# Sheet1.net
KiCad netlist of a schematic drawn in Altium Designer
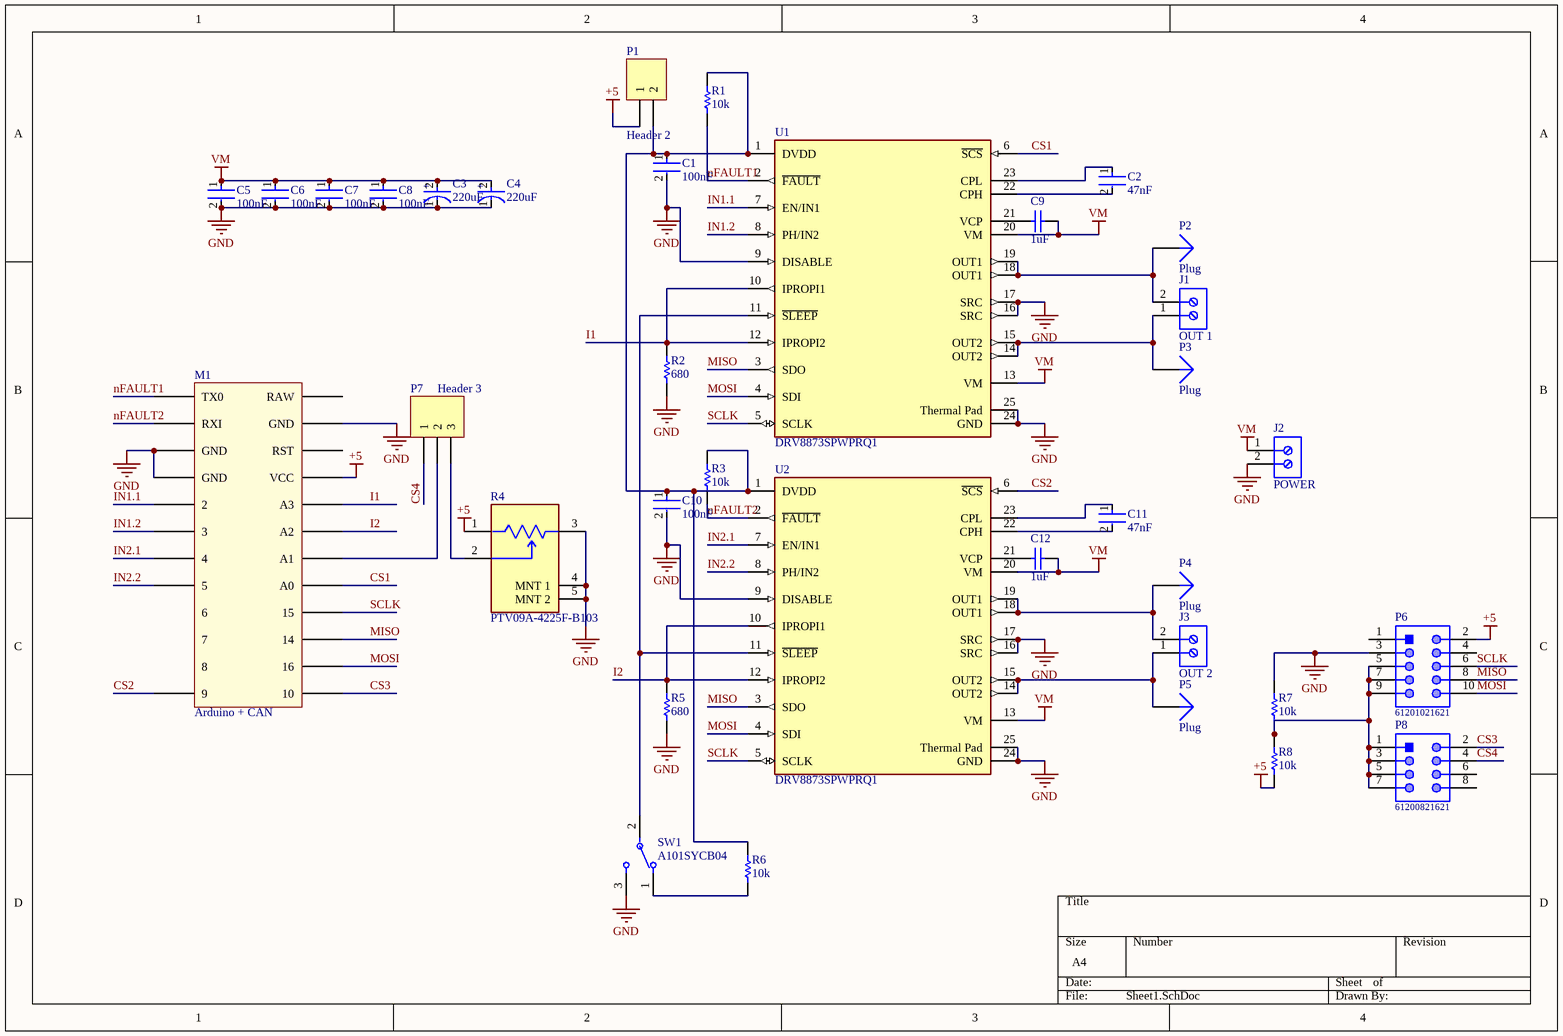
[diagram p0: Sheet1.SchDoc]

(export (version "E")
  (design (tool "Eeschema 10.0.6"))
  (components
    (comp (ref "C1")
      (value "100nF")
      (footprint "FP-0805-L_2_01_0_2-W_1_25-IPC_B")
      (description "General Purpose Ceramic Capacitor, 0805, 100nF, 10%, X7R, 15%, 100V")
      (fields (field (name "VOLTAGE") "100V") (field (name "TOLERANCE") "10%"))
      (libsource (lib "Altium Content Vault") (part "b4654b650e69147ec39a6b967a45e02"))
    )
    (comp (ref "C2")
      (value "47nF")
      (footprint "FP-C0805C-DN-MFG")
      (description "CAP CER 0.047UF 50V X7R 0805")
      (fields
        (field (name "MANUFACTURER PART NUMBER") "C0805C473K5RACTU")
        (field (name "OCTOPART") "https://octopart.com/c0805c473k5ractu-kemet-138387")
      )
      (libsource (lib "Altium Content Vault") (part "b4654b650e69147ec39a6b967a45e02"))
    )
    (comp (ref "C3")
      (value "220uF")
      (footprint "FP-UWT1V221MNL1GS-MFG")
      (description "CAP ALUM 220UF 20% 35V SMD")
      (fields (field (name "VOLTAGE") "35V") (field (name "TOLERANCE") "20%"))
      (libsource (lib "Altium Content Vault") (part "a00bbbee19879c290e62620ae7e47b1"))
    )
    (comp (ref "C4")
      (value "220uF")
      (footprint "FP-UWT1V221MNL1GS-MFG")
      (description "CAP ALUM 220UF 20% 35V SMD")
      (fields (field (name "VOLTAGE") "35V") (field (name "TOLERANCE") "20%"))
      (libsource (lib "Altium Content Vault") (part "a00bbbee19879c290e62620ae7e47b1"))
    )
    (comp (ref "C5")
      (value "100nF")
      (footprint "FP-0805-L_2_01_0_2-W_1_25-IPC_B")
      (description "General Purpose Ceramic Capacitor, 0805, 100nF, 10%, X7R, 15%, 100V")
      (fields (field (name "VOLTAGE") "100V") (field (name "TOLERANCE") "10%"))
      (libsource (lib "Altium Content Vault") (part "b4654b650e69147ec39a6b967a45e02"))
    )
    (comp (ref "C6")
      (value "100nF")
      (footprint "FP-0805-L_2_01_0_2-W_1_25-IPC_B")
      (description "General Purpose Ceramic Capacitor, 0805, 100nF, 10%, X7R, 15%, 100V")
      (fields (field (name "VOLTAGE") "100V") (field (name "TOLERANCE") "10%"))
      (libsource (lib "Altium Content Vault") (part "b4654b650e69147ec39a6b967a45e02"))
    )
    (comp (ref "C7")
      (value "100nF")
      (footprint "FP-0805-L_2_01_0_2-W_1_25-IPC_B")
      (description "General Purpose Ceramic Capacitor, 0805, 100nF, 10%, X7R, 15%, 100V")
      (fields (field (name "VOLTAGE") "100V") (field (name "TOLERANCE") "10%"))
      (libsource (lib "Altium Content Vault") (part "b4654b650e69147ec39a6b967a45e02"))
    )
    (comp (ref "C8")
      (value "100nF")
      (footprint "FP-0805-L_2_01_0_2-W_1_25-IPC_B")
      (description "General Purpose Ceramic Capacitor, 0805, 100nF, 10%, X7R, 15%, 100V")
      (fields (field (name "VOLTAGE") "100V") (field (name "TOLERANCE") "10%"))
      (libsource (lib "Altium Content Vault") (part "b4654b650e69147ec39a6b967a45e02"))
    )
    (comp (ref "C9")
      (value "1uF")
      (footprint "CAPC2013X145X50LL20T25")
      (fields (field (name "MANUFACTURER") "Kemet") (field (name "PART NUMBER") "C0805C105K4PACTU"))
      (libsource (lib "Altium Content Vault") (part "CAP"))
    )
    (comp (ref "C10")
      (value "100nF")
      (footprint "FP-0805-L_2_01_0_2-W_1_25-IPC_B")
      (description "General Purpose Ceramic Capacitor, 0805, 100nF, 10%, X7R, 15%, 100V")
      (fields (field (name "VOLTAGE") "100V") (field (name "TOLERANCE") "10%"))
      (libsource (lib "Altium Content Vault") (part "b4654b650e69147ec39a6b967a45e02"))
    )
    (comp (ref "C11")
      (value "47nF")
      (footprint "FP-C0805C-DN-MFG")
      (description "CAP CER 0.047UF 50V X7R 0805")
      (fields
        (field (name "MANUFACTURER PART NUMBER") "C0805C473K5RACTU")
        (field (name "OCTOPART") "https://octopart.com/c0805c473k5ractu-kemet-138387")
      )
      (libsource (lib "Altium Content Vault") (part "b4654b650e69147ec39a6b967a45e02"))
    )
    (comp (ref "C12")
      (value "1uF")
      (footprint "CAPC2013X145X50LL20T25")
      (fields (field (name "MANUFACTURER") "Kemet") (field (name "PART NUMBER") "C0805C105K4PACTU"))
      (libsource (lib "Altium Content Vault") (part "CAP"))
    )
    (comp (ref "J1")
      (value "OUT 1")
      (footprint "691102710002")
      (fields (field (name "VOLTAGE") "300V"))
      (libsource (lib "Altium Content Vault") (part "TBL - 1R - 02P - Screw"))
    )
    (comp (ref "J2")
      (value "POWER")
      (footprint "691102710002")
      (fields (field (name "VOLTAGE") "300V"))
      (libsource (lib "Altium Content Vault") (part "TBL - 1R - 02P - Screw"))
    )
    (comp (ref "J3")
      (value "OUT 2")
      (footprint "691102710002")
      (fields (field (name "VOLTAGE") "300V"))
      (libsource (lib "Altium Content Vault") (part "TBL - 1R - 02P - Screw"))
    )
    (comp (ref "M1")
      (value "Arduino + CAN")
      (footprint "PCBComponent_1")
      (description "Arduino Pro Micro + CAN Shield")
      (libsource (lib "Arduino") (part "Arduino"))
    )
    (comp (ref "P1")
      (value "Header 2")
      (footprint "HDR1X2")
      (description "Header, 2-Pin")
      (fields (field (name "PUBLISHER") "Altium Limited"))
      (libsource (lib "Miscellaneous Connectors") (part "Header 2"))
    )
    (comp (ref "P2")
      (value "Plug")
      (footprint "PIN1")
      (fields (field (name "PUBLISHER") "Altium Limited"))
      (libsource (lib "Miscellaneous Connectors") (part "Plug"))
    )
    (comp (ref "P3")
      (value "Plug")
      (footprint "PIN1")
      (fields (field (name "PUBLISHER") "Altium Limited"))
      (libsource (lib "Miscellaneous Connectors") (part "Plug"))
    )
    (comp (ref "P4")
      (value "Plug")
      (footprint "PIN1")
      (fields (field (name "PUBLISHER") "Altium Limited"))
      (libsource (lib "Miscellaneous Connectors") (part "Plug"))
    )
    (comp (ref "P5")
      (value "Plug")
      (footprint "PIN1")
      (fields (field (name "PUBLISHER") "Altium Limited"))
      (libsource (lib "Miscellaneous Connectors") (part "Plug"))
    )
    (comp (ref "P6")
      (value "61201021621")
      (footprint "61201021621")
      (description "Male Box Header WR-BHD, THT, Vertical, pitch 2.54 mm, 10 pins")
      (fields (field (name "MANUFACTURER") "Wurth Elektronik") (field (name "PUBLISHER") "WurthElektronik"))
      (libsource (lib "Altium Content Vault") (part "WE-CN-2P-M-R10"))
    )
    (comp (ref "P7")
      (value "Header 3")
      (footprint "HDR1X3")
      (description "Header, 3-Pin")
      (fields (field (name "PUBLISHER") "Altium Limited"))
      (libsource (lib "Miscellaneous Connectors") (part "Header 3"))
    )
    (comp (ref "P8")
      (value "61200821621")
      (footprint "61200821621")
      (description "Male Box Header WR-BHD, THT, Vertical, pitch 2.54 mm, 8 pins")
      (fields (field (name "MANUFACTURER") "Wurth Elektronik") (field (name "PUBLISHER") "WurthElektronik"))
      (libsource (lib "Altium Content Vault") (part "WE-CN-2P-M-R8"))
    )
    (comp (ref "R1")
      (value "10k")
      (footprint "RESC2013X60X35NL10T20")
      (description "Chip Resistor, 10 KOhm, +/- 1%, 0.125 W, -55 to 155 degC, 0805 (2012 Metric), RoHS, Tape and Reel")
      (fields (field (name "MANUFACTURER") "Yageo"))
      (libsource (lib "Altium Content Vault") (part "RES-2"))
    )
    (comp (ref "R2")
      (value "680")
      (footprint "RESC2013X60X35NL10T20")
      (description "Chip Resistor, 10 KOhm, +/- 1%, 0.125 W, -55 to 155 degC, 0805 (2012 Metric), RoHS, Tape and Reel")
      (fields (field (name "MANUFACTURER") "Yageo"))
      (libsource (lib "Altium Content Vault") (part "RES-2"))
    )
    (comp (ref "R3")
      (value "10k")
      (footprint "RESC2013X60X35NL10T20")
      (description "Chip Resistor, 10 KOhm, +/- 1%, 0.125 W, -55 to 155 degC, 0805 (2012 Metric), RoHS, Tape and Reel")
      (fields (field (name "MANUFACTURER") "Yageo"))
      (libsource (lib "Altium Content Vault") (part "RES-2"))
    )
    (comp (ref "R4")
      (value "PTV09A-4225F-B103")
      (footprint "FP-PTV09A-4-MFG")
      (description "POT 10K OHM 1/20W CARBON LINEAR")
      (fields (field (name "TOLERANCE") "20%"))
      (libsource (lib "Altium Content Vault") (part "705d11b747745a787204d796a5f3d12"))
    )
    (comp (ref "R5")
      (value "680")
      (footprint "RESC2013X60X35NL10T20")
      (description "Chip Resistor, 10 KOhm, +/- 1%, 0.125 W, -55 to 155 degC, 0805 (2012 Metric), RoHS, Tape and Reel")
      (fields (field (name "MANUFACTURER") "Yageo"))
      (libsource (lib "Altium Content Vault") (part "RES-2"))
    )
    (comp (ref "R6")
      (value "10k")
      (footprint "RESC2013X60X35NL10T20")
      (description "Chip Resistor, 10 KOhm, +/- 1%, 0.125 W, -55 to 155 degC, 0805 (2012 Metric), RoHS, Tape and Reel")
      (fields (field (name "MANUFACTURER") "Yageo"))
      (libsource (lib "Altium Content Vault") (part "RES-2"))
    )
    (comp (ref "R7")
      (value "10k")
      (footprint "RESC2013X60X35NL10T20")
      (description "Chip Resistor, 10 KOhm, +/- 1%, 0.125 W, -55 to 155 degC, 0805 (2012 Metric), RoHS, Tape and Reel")
      (fields (field (name "MANUFACTURER") "Yageo"))
      (libsource (lib "Altium Content Vault") (part "RES-2"))
    )
    (comp (ref "R8")
      (value "10k")
      (footprint "RESC2013X60X35NL10T20")
      (description "Chip Resistor, 10 KOhm, +/- 1%, 0.125 W, -55 to 155 degC, 0805 (2012 Metric), RoHS, Tape and Reel")
      (fields (field (name "MANUFACTURER") "Yageo"))
      (libsource (lib "Altium Content Vault") (part "RES-2"))
    )
    (comp (ref "SW1")
      (value "A101SYCB04")
      (footprint "FP-A101SYCB04-MFG")
      (description "SWITCH TOGGLE SPDT 0.4VA 20V")
      (libsource (lib "Altium Content Vault") (part "52c419afdc2a387c7d548259a9aeefb"))
    )
    (comp (ref "U1")
      (value "DRV8873SPWPRQ1")
      (footprint "FP-PWP0024J-MFG")
      (description "IC MTRDRV UNIPLR 0-5.5V 24HTSSOP")
      (libsource (lib "Altium Content Vault") (part "639cfc0396780f9562c68c0b1c9b09f"))
    )
    (comp (ref "U2")
      (value "DRV8873SPWPRQ1")
      (footprint "FP-PWP0024J-MFG")
      (description "IC MTRDRV UNIPLR 0-5.5V 24HTSSOP")
      (libsource (lib "Altium Content Vault") (part "639cfc0396780f9562c68c0b1c9b09f"))
    )
  )
  (nets
    (net (code "1") (name "+5") (class "Default")
      (node (ref "M1") (pin "21") (pinfunction "VCC_21") (pintype "passive"))
      (node (ref "P1") (pin "1") (pinfunction "1_1") (pintype "passive"))
      (node (ref "P6") (pin "2") (pinfunction "2_2") (pintype "passive"))
      (node (ref "R4") (pin "1") (pinfunction "1_1") (pintype "passive"))
      (node (ref "R8") (pin "1") (pinfunction "1_1") (pintype "passive"))
    )
    (net (code "2") (name "/CS1") (class "Default")
      (node (ref "M1") (pin "17") (pinfunction "A0_17") (pintype "passive"))
      (node (ref "U1") (pin "6") (pinfunction "~{SCS}_6") (pintype "input"))
    )
    (net (code "3") (name "/CS2") (class "Default")
      (node (ref "M1") (pin "12") (pinfunction "9_12") (pintype "passive"))
      (node (ref "U2") (pin "6") (pinfunction "~{SCS}_6") (pintype "input"))
    )
    (net (code "4") (name "/CS3") (class "Default")
      (node (ref "M1") (pin "13") (pinfunction "10_13") (pintype "passive"))
      (node (ref "P8") (pin "2") (pinfunction "2_2") (pintype "passive"))
    )
    (net (code "5") (name "/CS4") (class "Default")
      (node (ref "P7") (pin "1") (pinfunction "1_1") (pintype "passive"))
      (node (ref "P8") (pin "4") (pinfunction "4_4") (pintype "passive"))
    )
    (net (code "6") (name "/I1") (class "Default")
      (node (ref "M1") (pin "20") (pinfunction "A3_20") (pintype "passive"))
      (node (ref "R2") (pin "2") (pinfunction "2_2") (pintype "passive"))
      (node (ref "U1") (pin "10") (pinfunction "IPROPI1_10") (pintype "output"))
      (node (ref "U1") (pin "12") (pinfunction "IPROPI2_12") (pintype "input"))
    )
    (net (code "7") (name "/I2") (class "Default")
      (node (ref "M1") (pin "19") (pinfunction "A2_19") (pintype "passive"))
      (node (ref "R5") (pin "2") (pinfunction "2_2") (pintype "passive"))
      (node (ref "U2") (pin "10") (pinfunction "IPROPI1_10") (pintype "output"))
      (node (ref "U2") (pin "12") (pinfunction "IPROPI2_12") (pintype "input"))
    )
    (net (code "8") (name "/IN1.1") (class "Default")
      (node (ref "M1") (pin "5") (pinfunction "2_5") (pintype "passive"))
      (node (ref "U1") (pin "7") (pinfunction "EN/IN1_7") (pintype "input"))
    )
    (net (code "9") (name "/IN1.2") (class "Default")
      (node (ref "M1") (pin "6") (pinfunction "3_6") (pintype "passive"))
      (node (ref "U1") (pin "8") (pinfunction "PH/IN2_8") (pintype "input"))
    )
    (net (code "10") (name "/IN2.1") (class "Default")
      (node (ref "M1") (pin "7") (pinfunction "4_7") (pintype "passive"))
      (node (ref "U2") (pin "7") (pinfunction "EN/IN1_7") (pintype "input"))
    )
    (net (code "11") (name "/IN2.2") (class "Default")
      (node (ref "M1") (pin "8") (pinfunction "5_8") (pintype "passive"))
      (node (ref "U2") (pin "8") (pinfunction "PH/IN2_8") (pintype "input"))
    )
    (net (code "12") (name "/MISO") (class "Default")
      (node (ref "M1") (pin "15") (pinfunction "14_15") (pintype "passive"))
      (node (ref "P6") (pin "8") (pinfunction "8_8") (pintype "passive"))
      (node (ref "U1") (pin "3") (pinfunction "SDO_3") (pintype "output"))
      (node (ref "U2") (pin "3") (pinfunction "SDO_3") (pintype "output"))
    )
    (net (code "13") (name "/MOSI") (class "Default")
      (node (ref "M1") (pin "14") (pinfunction "16_14") (pintype "passive"))
      (node (ref "P6") (pin "10") (pinfunction "10_10") (pintype "passive"))
      (node (ref "U1") (pin "4") (pinfunction "SDI_4") (pintype "input"))
      (node (ref "U2") (pin "4") (pinfunction "SDI_4") (pintype "input"))
    )
    (net (code "14") (name "/SCLK") (class "Default")
      (node (ref "M1") (pin "16") (pinfunction "15_16") (pintype "passive"))
      (node (ref "P6") (pin "6") (pinfunction "6_6") (pintype "passive"))
      (node (ref "U1") (pin "5") (pinfunction "SCLK_5") (pintype "bidirectional"))
      (node (ref "U2") (pin "5") (pinfunction "SCLK_5") (pintype "bidirectional"))
    )
    (net (code "15") (name "/nFAULT1") (class "Default")
      (node (ref "M1") (pin "1") (pinfunction "TX0_1") (pintype "passive"))
      (node (ref "R1") (pin "1") (pinfunction "1_1") (pintype "passive"))
      (node (ref "U1") (pin "2") (pinfunction "~{FAULT}_2") (pintype "output"))
    )
    (net (code "16") (name "/nFAULT2") (class "Default")
      (node (ref "M1") (pin "2") (pinfunction "RXI_2") (pintype "passive"))
      (node (ref "R3") (pin "1") (pinfunction "1_1") (pintype "passive"))
      (node (ref "U2") (pin "2") (pinfunction "~{FAULT}_2") (pintype "output"))
    )
    (net (code "17") (name "GND") (class "Default")
      (node (ref "C1") (pin "2") (pinfunction "2_2") (pintype "passive"))
      (node (ref "C10") (pin "2") (pinfunction "2_2") (pintype "passive"))
      (node (ref "C3") (pin "1") (pinfunction "C_1") (pintype "passive"))
      (node (ref "C4") (pin "1") (pinfunction "C_1") (pintype "passive"))
      (node (ref "C5") (pin "2") (pinfunction "2_2") (pintype "passive"))
      (node (ref "C6") (pin "2") (pinfunction "2_2") (pintype "passive"))
      (node (ref "C7") (pin "2") (pinfunction "2_2") (pintype "passive"))
      (node (ref "C8") (pin "2") (pinfunction "2_2") (pintype "passive"))
      (node (ref "J2") (pin "2") (pinfunction "2_2") (pintype "passive"))
      (node (ref "M1") (pin "23") (pinfunction "GND_23") (pintype "passive"))
      (node (ref "M1") (pin "3") (pinfunction "GND_3") (pintype "passive"))
      (node (ref "M1") (pin "4") (pinfunction "GND_4") (pintype "passive"))
      (node (ref "P6") (pin "3") (pinfunction "3_3") (pintype "passive"))
      (node (ref "R2") (pin "1") (pinfunction "1_1") (pintype "passive"))
      (node (ref "R4") (pin "3") (pinfunction "3_3") (pintype "passive"))
      (node (ref "R4") (pin "4") (pinfunction "MNT_1_4") (pintype "passive"))
      (node (ref "R4") (pin "5") (pinfunction "MNT_2_5") (pintype "passive"))
      (node (ref "R5") (pin "1") (pinfunction "1_1") (pintype "passive"))
      (node (ref "R7") (pin "2") (pinfunction "2_2") (pintype "passive"))
      (node (ref "SW1") (pin "3") (pinfunction "3_3") (pintype "passive"))
      (node (ref "U1") (pin "16") (pinfunction "SRC_16") (pintype "output"))
      (node (ref "U1") (pin "17") (pinfunction "SRC_17") (pintype "output"))
      (node (ref "U1") (pin "24") (pinfunction "GND_24") (pintype "power_in"))
      (node (ref "U1") (pin "25") (pinfunction "Thermal_Pad_25") (pintype "power_in"))
      (node (ref "U1") (pin "9") (pinfunction "DISABLE_9") (pintype "input"))
      (node (ref "U2") (pin "16") (pinfunction "SRC_16") (pintype "output"))
      (node (ref "U2") (pin "17") (pinfunction "SRC_17") (pintype "output"))
      (node (ref "U2") (pin "24") (pinfunction "GND_24") (pintype "power_in"))
      (node (ref "U2") (pin "25") (pinfunction "Thermal_Pad_25") (pintype "power_in"))
      (node (ref "U2") (pin "9") (pinfunction "DISABLE_9") (pintype "input"))
    )
    (net (code "18") (name "Net-(J1-Pad1)") (class "Default")
      (node (ref "J1") (pin "1") (pinfunction "1_1") (pintype "passive"))
      (node (ref "P3") (pin "1") (pinfunction "1_1") (pintype "passive"))
      (node (ref "U1") (pin "14") (pinfunction "OUT2_14") (pintype "output"))
      (node (ref "U1") (pin "15") (pinfunction "OUT2_15") (pintype "output"))
    )
    (net (code "19") (name "Net-(J1-Pad2)") (class "Default")
      (node (ref "J1") (pin "2") (pinfunction "2_2") (pintype "passive"))
      (node (ref "P2") (pin "1") (pinfunction "1_1") (pintype "passive"))
      (node (ref "U1") (pin "18") (pinfunction "OUT1_18") (pintype "output"))
      (node (ref "U1") (pin "19") (pinfunction "OUT1_19") (pintype "output"))
    )
    (net (code "20") (name "Net-(J3-Pad1)") (class "Default")
      (node (ref "J3") (pin "1") (pinfunction "1_1") (pintype "passive"))
      (node (ref "P5") (pin "1") (pinfunction "1_1") (pintype "passive"))
      (node (ref "U2") (pin "14") (pinfunction "OUT2_14") (pintype "output"))
      (node (ref "U2") (pin "15") (pinfunction "OUT2_15") (pintype "output"))
    )
    (net (code "21") (name "Net-(J3-Pad2)") (class "Default")
      (node (ref "J3") (pin "2") (pinfunction "2_2") (pintype "passive"))
      (node (ref "P4") (pin "1") (pinfunction "1_1") (pintype "passive"))
      (node (ref "U2") (pin "18") (pinfunction "OUT1_18") (pintype "output"))
      (node (ref "U2") (pin "19") (pinfunction "OUT1_19") (pintype "output"))
    )
    (net (code "22") (name "Net-(M1-A1)") (class "Default")
      (node (ref "M1") (pin "18") (pinfunction "A1_18") (pintype "passive"))
      (node (ref "P7") (pin "2") (pinfunction "2_2") (pintype "passive"))
    )
    (net (code "23") (name "Net-(P6-Pad5)") (class "Default")
      (node (ref "P6") (pin "5") (pinfunction "5_5") (pintype "passive"))
      (node (ref "P6") (pin "7") (pinfunction "7_7") (pintype "passive"))
      (node (ref "P6") (pin "9") (pinfunction "9_9") (pintype "passive"))
      (node (ref "P8") (pin "1") (pinfunction "1_1") (pintype "passive"))
      (node (ref "P8") (pin "3") (pinfunction "3_3") (pintype "passive"))
      (node (ref "P8") (pin "5") (pinfunction "5_5") (pintype "passive"))
      (node (ref "P8") (pin "7") (pinfunction "7_7") (pintype "passive"))
      (node (ref "R7") (pin "1") (pinfunction "1_1") (pintype "passive"))
      (node (ref "R8") (pin "2") (pinfunction "2_2") (pintype "passive"))
    )
    (net (code "24") (name "Net-(P7-Pad3)") (class "Default")
      (node (ref "P7") (pin "3") (pinfunction "3_3") (pintype "passive"))
      (node (ref "R4") (pin "2") (pinfunction "2_2") (pintype "passive"))
    )
    (net (code "25") (name "Net-(R6-Pad1)") (class "Default")
      (node (ref "R6") (pin "1") (pinfunction "1_1") (pintype "passive"))
      (node (ref "SW1") (pin "1") (pinfunction "1_1") (pintype "passive"))
    )
    (net (code "26") (name "Net-(U1-CPH)") (class "Default")
      (node (ref "C2") (pin "2") (pinfunction "2_2") (pintype "passive"))
      (node (ref "U1") (pin "22") (pinfunction "CPH_22") (pintype "power_in"))
    )
    (net (code "27") (name "Net-(U1-CPL)") (class "Default")
      (node (ref "C2") (pin "1") (pinfunction "1_1") (pintype "passive"))
      (node (ref "U1") (pin "23") (pinfunction "CPL_23") (pintype "power_in"))
    )
    (net (code "28") (name "Net-(U1-DVDD)") (class "Default")
      (node (ref "C1") (pin "1") (pinfunction "1_1") (pintype "passive"))
      (node (ref "C10") (pin "1") (pinfunction "1_1") (pintype "passive"))
      (node (ref "P1") (pin "2") (pinfunction "2_2") (pintype "passive"))
      (node (ref "R1") (pin "2") (pinfunction "2_2") (pintype "passive"))
      (node (ref "R3") (pin "2") (pinfunction "2_2") (pintype "passive"))
      (node (ref "R6") (pin "2") (pinfunction "2_2") (pintype "passive"))
      (node (ref "U1") (pin "1") (pinfunction "DVDD_1") (pintype "power_in"))
      (node (ref "U2") (pin "1") (pinfunction "DVDD_1") (pintype "power_in"))
    )
    (net (code "29") (name "Net-(U1-VCP)") (class "Default")
      (node (ref "C9") (pin "1") (pinfunction "1_1") (pintype "passive"))
      (node (ref "U1") (pin "21") (pinfunction "VCP_21") (pintype "power_in"))
    )
    (net (code "30") (name "Net-(U1-~{SLEEP})") (class "Default")
      (node (ref "SW1") (pin "2") (pinfunction "2_2") (pintype "passive"))
      (node (ref "U1") (pin "11") (pinfunction "~{SLEEP}_11") (pintype "input"))
      (node (ref "U2") (pin "11") (pinfunction "~{SLEEP}_11") (pintype "input"))
    )
    (net (code "31") (name "Net-(U2-CPH)") (class "Default")
      (node (ref "C11") (pin "2") (pinfunction "2_2") (pintype "passive"))
      (node (ref "U2") (pin "22") (pinfunction "CPH_22") (pintype "power_in"))
    )
    (net (code "32") (name "Net-(U2-CPL)") (class "Default")
      (node (ref "C11") (pin "1") (pinfunction "1_1") (pintype "passive"))
      (node (ref "U2") (pin "23") (pinfunction "CPL_23") (pintype "power_in"))
    )
    (net (code "33") (name "Net-(U2-VCP)") (class "Default")
      (node (ref "C12") (pin "1") (pinfunction "1_1") (pintype "passive"))
      (node (ref "U2") (pin "21") (pinfunction "VCP_21") (pintype "power_in"))
    )
    (net (code "34") (name "VM") (class "Default")
      (node (ref "C12") (pin "2") (pinfunction "2_2") (pintype "passive"))
      (node (ref "C3") (pin "2") (pinfunction "A_2") (pintype "passive"))
      (node (ref "C4") (pin "2") (pinfunction "A_2") (pintype "passive"))
      (node (ref "C5") (pin "1") (pinfunction "1_1") (pintype "passive"))
      (node (ref "C6") (pin "1") (pinfunction "1_1") (pintype "passive"))
      (node (ref "C7") (pin "1") (pinfunction "1_1") (pintype "passive"))
      (node (ref "C8") (pin "1") (pinfunction "1_1") (pintype "passive"))
      (node (ref "C9") (pin "2") (pinfunction "2_2") (pintype "passive"))
      (node (ref "J2") (pin "1") (pinfunction "1_1") (pintype "passive"))
      (node (ref "U1") (pin "13") (pinfunction "VM_13") (pintype "power_in"))
      (node (ref "U1") (pin "20") (pinfunction "VM_20") (pintype "power_in"))
      (node (ref "U2") (pin "13") (pinfunction "VM_13") (pintype "power_in"))
      (node (ref "U2") (pin "20") (pinfunction "VM_20") (pintype "power_in"))
    )
    (net (code "35") (name "unconnected-(M1-6-Pad9)") (class "Default")
      (node (ref "M1") (pin "9") (pinfunction "6_9") (pintype "passive"))
    )
    (net (code "36") (name "unconnected-(M1-7-Pad10)") (class "Default")
      (node (ref "M1") (pin "10") (pinfunction "7_10") (pintype "passive"))
    )
    (net (code "37") (name "unconnected-(M1-8-Pad11)") (class "Default")
      (node (ref "M1") (pin "11") (pinfunction "8_11") (pintype "passive"))
    )
    (net (code "38") (name "unconnected-(M1-RAW-Pad24)") (class "Default")
      (node (ref "M1") (pin "24") (pinfunction "RAW_24") (pintype "passive"))
    )
    (net (code "39") (name "unconnected-(M1-RST-Pad22)") (class "Default")
      (node (ref "M1") (pin "22") (pinfunction "RST_22") (pintype "passive"))
    )
    (net (code "40") (name "unconnected-(P6-Pad1)") (class "Default")
      (node (ref "P6") (pin "1") (pinfunction "1_1") (pintype "passive"))
    )
    (net (code "41") (name "unconnected-(P6-Pad4)") (class "Default")
      (node (ref "P6") (pin "4") (pinfunction "4_4") (pintype "passive"))
    )
    (net (code "42") (name "unconnected-(P8-Pad6)") (class "Default")
      (node (ref "P8") (pin "6") (pinfunction "6_6") (pintype "passive"))
    )
    (net (code "43") (name "unconnected-(P8-Pad8)") (class "Default")
      (node (ref "P8") (pin "8") (pinfunction "8_8") (pintype "passive"))
    )
  )
)
